# CAN_Tranceiver.net
KiCad netlist of a schematic drawn in Altium Designer
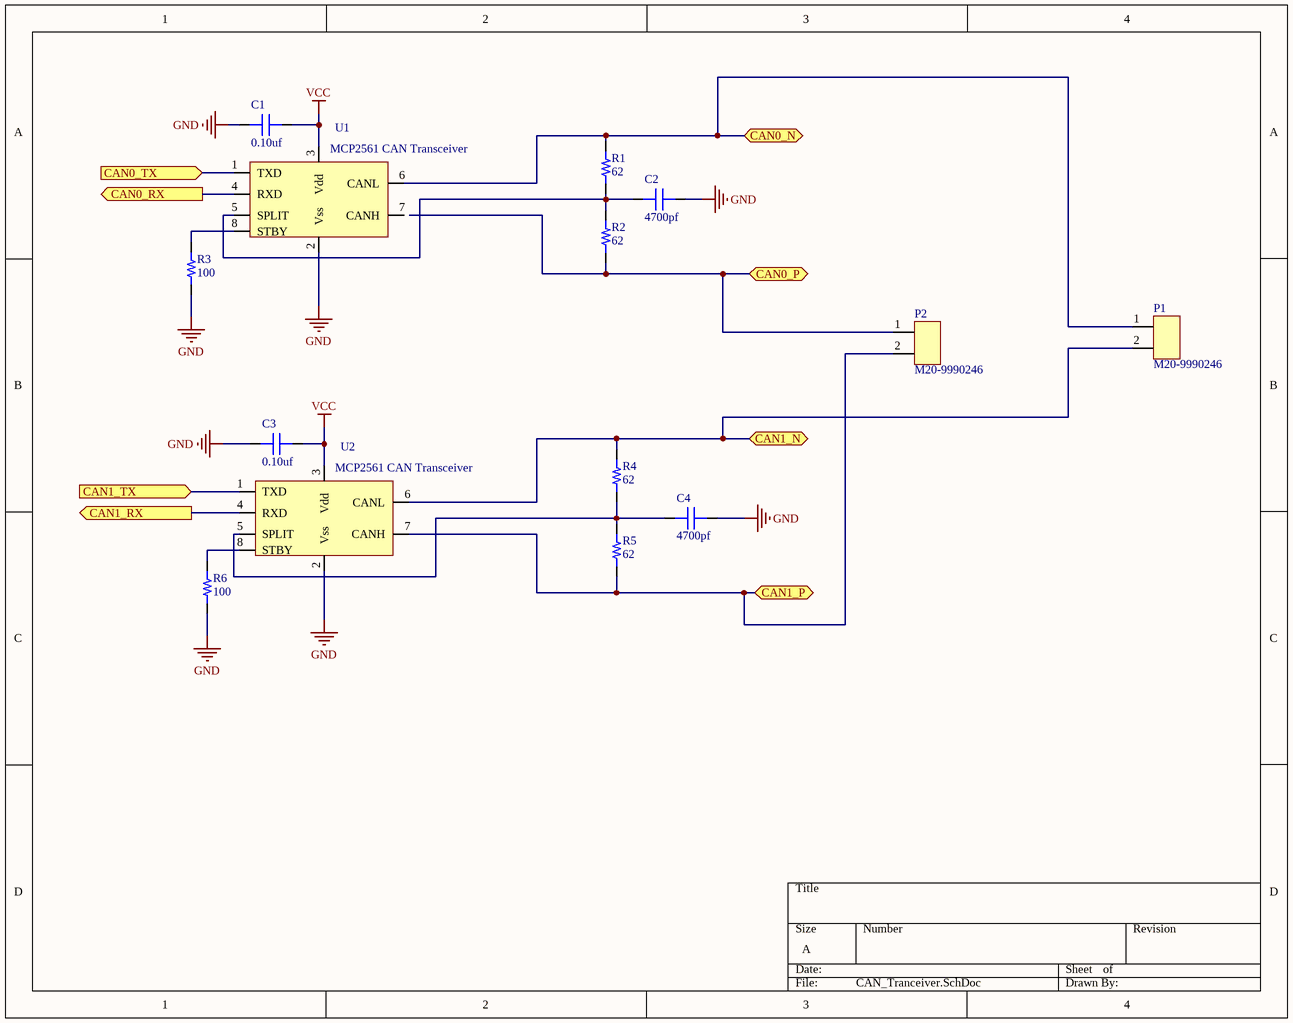
[diagram p0: CAN_Tranceiver.SchDoc]

(export (version "E")
  (design (tool "Eeschema 10.0.6"))
  (components
    (comp (ref "C1")
      (value "0.10uf")
      (footprint "CAP 0603/1608")
      (fields
        (field (name "Comment") "Capacitor MLCC 0.10uf 50V CAP 0603/1608")
        (field (name "CREATED_BY") "Nick Mah")
      )
      (libsource (lib "Altium-Lib") (part "Capacitor"))
    )
    (comp (ref "C2")
      (value "4700pf")
      (footprint "CAP 0603/1608")
      (fields
        (field (name "Comment") "Capacitor MLCC 4700pf 50V CAP 0603/1608")
        (field (name "CREATED_BY") "Nick Mah")
      )
      (libsource (lib "Altium-Lib") (part "Capacitor"))
    )
    (comp (ref "C3")
      (value "0.10uf")
      (footprint "CAP 0603/1608")
      (fields
        (field (name "Comment") "Capacitor MLCC 0.10uf 50V CAP 0603/1608")
        (field (name "CREATED_BY") "Nick Mah")
      )
      (libsource (lib "Altium-Lib") (part "Capacitor"))
    )
    (comp (ref "C4")
      (value "4700pf")
      (footprint "CAP 0603/1608")
      (fields
        (field (name "Comment") "Capacitor MLCC 4700pf 50V CAP 0603/1608")
        (field (name "CREATED_BY") "Nick Mah")
      )
      (libsource (lib "Altium-Lib") (part "Capacitor"))
    )
    (comp (ref "P1")
      (value "M20-9990246")
      (footprint "M20-9990246")
      (description "2 Pin VCC Power Header, Male")
      (fields (field (name "CREATED_BY") "Austin") (field (name "UPDATED_BY") "Null"))
      (libsource (lib "Altium-Lib") (part "M20-9990246"))
    )
    (comp (ref "P2")
      (value "M20-9990246")
      (footprint "M20-9990246")
      (description "2 Pin VCC Power Header, Male")
      (fields (field (name "CREATED_BY") "Austin") (field (name "UPDATED_BY") "Null"))
      (libsource (lib "Altium-Lib") (part "M20-9990246"))
    )
    (comp (ref "R1")
      (value "62")
      (footprint "RES 0603/1608")
      (fields
        (field (name "TOLERANCE") "5%")
        (field (name "POWER") "1/10W")
        (field (name "Comment") "Resistor 62 0603 1/10W 5%")
        (field (name "CREATED_BY") "Nick Mah")
      )
      (libsource (lib "Altium-Lib") (part "Resistor"))
    )
    (comp (ref "R2")
      (value "62")
      (footprint "RES 0603/1608")
      (fields
        (field (name "TOLERANCE") "5%")
        (field (name "POWER") "1/10W")
        (field (name "Comment") "Resistor 62 0603 1/10W 5%")
        (field (name "CREATED_BY") "Nick Mah")
      )
      (libsource (lib "Altium-Lib") (part "Resistor"))
    )
    (comp (ref "R3")
      (value "100")
      (footprint "RES 0603/1608")
      (fields
        (field (name "TOLERANCE") "10%")
        (field (name "POWER") "1/10W")
        (field (name "Comment") "Resistor 100 0603 1/10W 10%")
        (field (name "CREATED_BY") "Nick Mah")
      )
      (libsource (lib "Altium-Lib") (part "Resistor"))
    )
    (comp (ref "R4")
      (value "62")
      (footprint "RES 0603/1608")
      (fields
        (field (name "TOLERANCE") "5%")
        (field (name "POWER") "1/10W")
        (field (name "Comment") "Resistor 62 0603 1/10W 5%")
        (field (name "CREATED_BY") "Nick Mah")
      )
      (libsource (lib "Altium-Lib") (part "Resistor"))
    )
    (comp (ref "R5")
      (value "62")
      (footprint "RES 0603/1608")
      (fields
        (field (name "TOLERANCE") "5%")
        (field (name "POWER") "1/10W")
        (field (name "Comment") "Resistor 62 0603 1/10W 5%")
        (field (name "CREATED_BY") "Nick Mah")
      )
      (libsource (lib "Altium-Lib") (part "Resistor"))
    )
    (comp (ref "R6")
      (value "100")
      (footprint "RES 0603/1608")
      (fields
        (field (name "TOLERANCE") "10%")
        (field (name "POWER") "1/10W")
        (field (name "Comment") "Resistor 100 0603 1/10W 10%")
        (field (name "CREATED_BY") "Nick Mah")
      )
      (libsource (lib "Altium-Lib") (part "Resistor"))
    )
    (comp (ref "U1")
      (value "MCP2561 CAN Transceiver")
      (footprint "SOIC-8")
      (fields (field (name "MFRPARTNO") "MCP2561") (field (name "CREATED_BY") "Angel Delgado"))
      (libsource (lib "Altium-Lib") (part "MCP2561 CAN Transceiver"))
    )
    (comp (ref "U2")
      (value "MCP2561 CAN Transceiver")
      (footprint "SOIC-8")
      (fields (field (name "MFRPARTNO") "MCP2561") (field (name "CREATED_BY") "Angel Delgado"))
      (libsource (lib "Altium-Lib") (part "MCP2561 CAN Transceiver"))
    )
  )
  (nets
    (net (code "1") (name "/CAN0_N") (class "Default")
      (node (ref "P1") (pin "1") (pintype "passive"))
      (node (ref "R1") (pin "1") (pinfunction "1_1") (pintype "passive"))
      (node (ref "U1") (pin "6") (pinfunction "CANL_6") (pintype "passive"))
    )
    (net (code "2") (name "/CAN0_P") (class "Default")
      (node (ref "P2") (pin "1") (pintype "passive"))
      (node (ref "R2") (pin "2") (pinfunction "2_2") (pintype "passive"))
    )
    (net (code "3") (name "/CAN0_RX") (class "Default")
      (node (ref "U1") (pin "4") (pinfunction "RXD_4") (pintype "passive"))
    )
    (net (code "4") (name "/CAN0_TX") (class "Default")
      (node (ref "U1") (pin "1") (pinfunction "TXD_1") (pintype "passive"))
    )
    (net (code "5") (name "/CAN1_N") (class "Default")
      (node (ref "P1") (pin "2") (pintype "passive"))
      (node (ref "R4") (pin "1") (pinfunction "1_1") (pintype "passive"))
      (node (ref "U2") (pin "6") (pinfunction "CANL_6") (pintype "passive"))
    )
    (net (code "6") (name "/CAN1_P") (class "Default")
      (node (ref "P2") (pin "2") (pintype "passive"))
      (node (ref "R5") (pin "2") (pinfunction "2_2") (pintype "passive"))
      (node (ref "U2") (pin "7") (pinfunction "CANH_7") (pintype "passive"))
    )
    (net (code "7") (name "/CAN1_RX") (class "Default")
      (node (ref "U2") (pin "4") (pinfunction "RXD_4") (pintype "passive"))
    )
    (net (code "8") (name "/CAN1_TX") (class "Default")
      (node (ref "U2") (pin "1") (pinfunction "TXD_1") (pintype "passive"))
    )
    (net (code "9") (name "GND") (class "Default")
      (node (ref "C1") (pin "1") (pinfunction "1_1") (pintype "passive"))
      (node (ref "C2") (pin "1") (pinfunction "1_1") (pintype "passive"))
      (node (ref "C3") (pin "1") (pinfunction "1_1") (pintype "passive"))
      (node (ref "C4") (pin "1") (pinfunction "1_1") (pintype "passive"))
      (node (ref "R3") (pin "1") (pinfunction "1_1") (pintype "passive"))
      (node (ref "R6") (pin "1") (pinfunction "1_1") (pintype "passive"))
      (node (ref "U1") (pin "2") (pinfunction "Vss_2") (pintype "passive"))
      (node (ref "U2") (pin "2") (pinfunction "Vss_2") (pintype "passive"))
    )
    (net (code "10") (name "Net-(U1-SPLIT)") (class "Default")
      (node (ref "C2") (pin "2") (pinfunction "2_2") (pintype "passive"))
      (node (ref "R1") (pin "2") (pinfunction "2_2") (pintype "passive"))
      (node (ref "R2") (pin "1") (pinfunction "1_1") (pintype "passive"))
      (node (ref "U1") (pin "5") (pinfunction "SPLIT_5") (pintype "passive"))
    )
    (net (code "11") (name "Net-(U1-STBY)") (class "Default")
      (node (ref "R3") (pin "2") (pinfunction "2_2") (pintype "passive"))
      (node (ref "U1") (pin "8") (pinfunction "STBY_8") (pintype "passive"))
    )
    (net (code "12") (name "Net-(U2-SPLIT)") (class "Default")
      (node (ref "C4") (pin "2") (pinfunction "2_2") (pintype "passive"))
      (node (ref "R4") (pin "2") (pinfunction "2_2") (pintype "passive"))
      (node (ref "R5") (pin "1") (pinfunction "1_1") (pintype "passive"))
      (node (ref "U2") (pin "5") (pinfunction "SPLIT_5") (pintype "passive"))
    )
    (net (code "13") (name "Net-(U2-STBY)") (class "Default")
      (node (ref "R6") (pin "2") (pinfunction "2_2") (pintype "passive"))
      (node (ref "U2") (pin "8") (pinfunction "STBY_8") (pintype "passive"))
    )
    (net (code "14") (name "VCC") (class "Default")
      (node (ref "C1") (pin "2") (pinfunction "2_2") (pintype "passive"))
      (node (ref "C3") (pin "2") (pinfunction "2_2") (pintype "passive"))
      (node (ref "U1") (pin "3") (pinfunction "Vdd_3") (pintype "passive"))
      (node (ref "U2") (pin "3") (pinfunction "Vdd_3") (pintype "passive"))
    )
    (net (code "15") (name "unconnected-(U1-CANH-Pad7)") (class "Default")
      (node (ref "U1") (pin "7") (pinfunction "CANH_7") (pintype "passive"))
    )
  )
)
